# mes-5.net
KiCad netlist of a schematic drawn in EAGLE
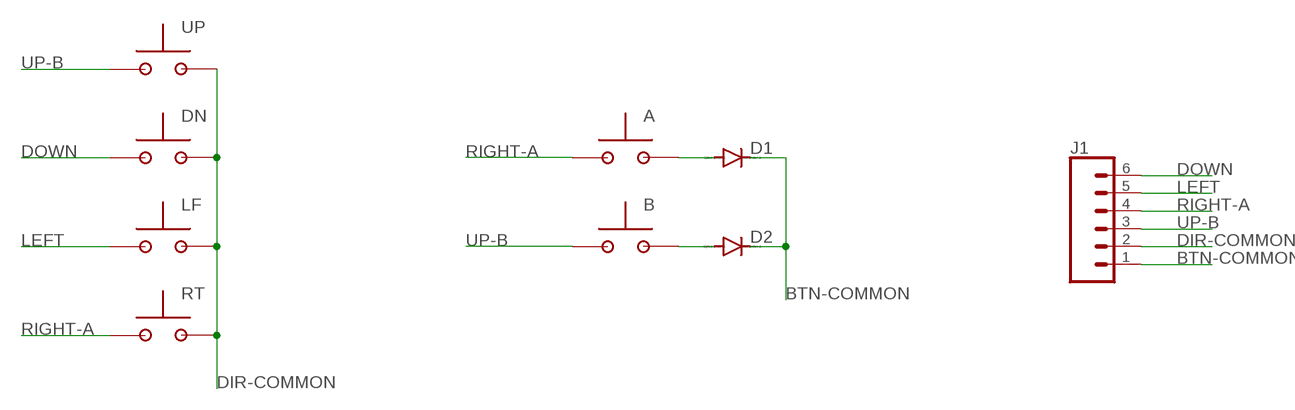
[diagram p0: schematic, sheet 1]

(export (version "E")
  (design (tool "Eeschema 10.0.6"))
  (components
    (comp (ref "A")
      (value "RUBBERBUTTON_CONTACTAREA_9MM")
      (footprint "eagle-import:RUBBERBUTTON_CONTACTAREA_9MM")
      (libsource (lib "eagle-import") (part "RUBBERBUTTON_CONTACTAREA_9MM"))
    )
    (comp (ref "B")
      (value "RUBBERBUTTON_CONTACTAREA_9MM")
      (footprint "eagle-import:RUBBERBUTTON_CONTACTAREA_9MM")
      (libsource (lib "eagle-import") (part "RUBBERBUTTON_CONTACTAREA_9MM"))
    )
    (comp (ref "D1")
      (value "1N4148DO35-7")
      (footprint "eagle-import:DO35-7")
      (libsource (lib "eagle-import") (part "1N4148DO35-7"))
    )
    (comp (ref "D2")
      (value "1N4148DO35-7")
      (footprint "eagle-import:DO35-7")
      (libsource (lib "eagle-import") (part "1N4148DO35-7"))
    )
    (comp (ref "DN")
      (value "RUBBERBUTTON_CONTACTAREA_9MM")
      (footprint "eagle-import:RUBBERBUTTON_CONTACTAREA_9MM")
      (libsource (lib "eagle-import") (part "RUBBERBUTTON_CONTACTAREA_9MM"))
    )
    (comp (ref "J1")
      (value "CONN_06LONGPADS")
      (footprint "eagle-import:1X06_LONGPADS")
      (libsource (lib "eagle-import") (part "CONN_06LONGPADS"))
    )
    (comp (ref "LF")
      (value "RUBBERBUTTON_CONTACTAREA_9MM")
      (footprint "eagle-import:RUBBERBUTTON_CONTACTAREA_9MM")
      (libsource (lib "eagle-import") (part "RUBBERBUTTON_CONTACTAREA_9MM"))
    )
    (comp (ref "RT")
      (value "RUBBERBUTTON_CONTACTAREA_9MM")
      (footprint "eagle-import:RUBBERBUTTON_CONTACTAREA_9MM")
      (libsource (lib "eagle-import") (part "RUBBERBUTTON_CONTACTAREA_9MM"))
    )
    (comp (ref "UP")
      (value "RUBBERBUTTON_CONTACTAREA_9MM")
      (footprint "eagle-import:RUBBERBUTTON_CONTACTAREA_9MM")
      (libsource (lib "eagle-import") (part "RUBBERBUTTON_CONTACTAREA_9MM"))
    )
  )
  (nets
    (net (code "1") (name "/BTN-COMMON") (class "Default")
      (node (ref "D1") (pin "C") (pinfunction "C_C") (pintype "passive"))
      (node (ref "D2") (pin "C") (pinfunction "C_C") (pintype "passive"))
      (node (ref "J1") (pin "1") (pinfunction "1_1") (pintype "passive"))
    )
    (net (code "2") (name "/DIR-COMMON") (class "Default")
      (node (ref "DN") (pin "B") (pinfunction "B_B") (pintype "bidirectional"))
      (node (ref "J1") (pin "2") (pinfunction "2_2") (pintype "passive"))
      (node (ref "LF") (pin "B") (pinfunction "B_B") (pintype "bidirectional"))
      (node (ref "RT") (pin "B") (pinfunction "B_B") (pintype "bidirectional"))
      (node (ref "UP") (pin "B") (pinfunction "B_B") (pintype "bidirectional"))
    )
    (net (code "3") (name "/DOWN") (class "Default")
      (node (ref "DN") (pin "A") (pinfunction "A_A") (pintype "bidirectional"))
      (node (ref "J1") (pin "6") (pinfunction "6_6") (pintype "passive"))
    )
    (net (code "4") (name "/LEFT") (class "Default")
      (node (ref "J1") (pin "5") (pinfunction "5_5") (pintype "passive"))
      (node (ref "LF") (pin "A") (pinfunction "A_A") (pintype "bidirectional"))
    )
    (net (code "5") (name "/RIGHT-A") (class "Default")
      (node (ref "A") (pin "A") (pinfunction "A_A") (pintype "bidirectional"))
      (node (ref "J1") (pin "4") (pinfunction "4_4") (pintype "passive"))
      (node (ref "RT") (pin "A") (pinfunction "A_A") (pintype "bidirectional"))
    )
    (net (code "6") (name "/UP-B") (class "Default")
      (node (ref "B") (pin "A") (pinfunction "A_A") (pintype "bidirectional"))
      (node (ref "J1") (pin "3") (pinfunction "3_3") (pintype "passive"))
      (node (ref "UP") (pin "A") (pinfunction "A_A") (pintype "bidirectional"))
    )
    (net (code "7") (name "Net-(A-PadB)") (class "Default")
      (node (ref "A") (pin "B") (pinfunction "B_B") (pintype "bidirectional"))
      (node (ref "D1") (pin "A") (pinfunction "A_A") (pintype "passive"))
    )
    (net (code "8") (name "Net-(B-PadB)") (class "Default")
      (node (ref "B") (pin "B") (pinfunction "B_B") (pintype "bidirectional"))
      (node (ref "D2") (pin "A") (pinfunction "A_A") (pintype "passive"))
    )
  )
)
